# schematic.net
KiCad netlist of a schematic drawn in EAGLE
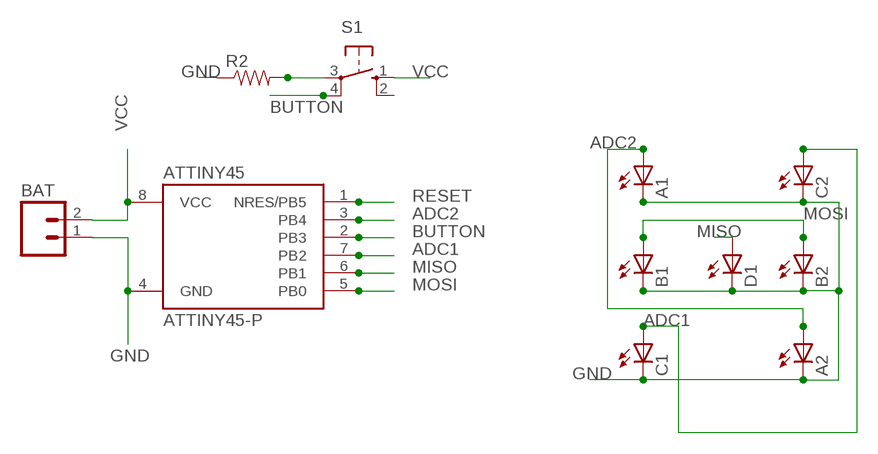
[diagram p0: schematic, sheet 1]

(export (version "E")
  (design (tool "Eeschema 10.0.6"))
  (components
    (comp (ref "A1")
      (value "LED5MM")
      (footprint "eagle-import:LED5MM")
      (libsource (lib "eagle-import") (part "LED5MM"))
    )
    (comp (ref "A2")
      (value "LED5MM")
      (footprint "eagle-import:LED5MM")
      (libsource (lib "eagle-import") (part "LED5MM"))
    )
    (comp (ref "ATTINY45")
      (value "ATTINY45-P")
      (footprint "eagle-import:PDIP08_300MIL")
      (libsource (lib "eagle-import") (part "ATTINY45P-"))
    )
    (comp (ref "B1")
      (value "LED5MM")
      (footprint "eagle-import:LED5MM")
      (libsource (lib "eagle-import") (part "LED5MM"))
    )
    (comp (ref "B2")
      (value "LED5MM")
      (footprint "eagle-import:LED5MM")
      (libsource (lib "eagle-import") (part "LED5MM"))
    )
    (comp (ref "BAT")
      (value "M02PTH")
      (footprint "eagle-import:1X02")
      (libsource (lib "eagle-import") (part "M02PTH"))
    )
    (comp (ref "C1")
      (value "LED5MM")
      (footprint "eagle-import:LED5MM")
      (libsource (lib "eagle-import") (part "LED5MM"))
    )
    (comp (ref "C2")
      (value "LED5MM")
      (footprint "eagle-import:LED5MM")
      (libsource (lib "eagle-import") (part "LED5MM"))
    )
    (comp (ref "D1")
      (value "LED5MM")
      (footprint "eagle-import:LED5MM")
      (libsource (lib "eagle-import") (part "LED5MM"))
    )
    (comp (ref "R2")
      (value "10KOHM-1/6W-5%(PTH)KIT")
      (footprint "eagle-import:AXIAL-0.3-KIT")
      (libsource (lib "eagle-import") (part "10KOHM-1/6W-5%(PTH)KIT"))
    )
    (comp (ref "S1")
      (value "40-XX")
      (footprint "eagle-import:B3F-40XX")
      (fields (field (name "MF") "OMRON COMPONENTS USA") (field (name "MPN") "B3F-4000"))
      (libsource (lib "eagle-import") (part "40-XX"))
    )
  )
  (nets
    (net (code "1") (name "/ADC1") (class "Default")
      (node (ref "ATTINY45") (pin "7") (pinfunction "PB2_7") (pintype "bidirectional"))
      (node (ref "C1") (pin "A") (pinfunction "A_A") (pintype "passive"))
      (node (ref "C2") (pin "A") (pinfunction "A_A") (pintype "passive"))
    )
    (net (code "2") (name "/ADC2") (class "Default")
      (node (ref "A1") (pin "A") (pinfunction "A_A") (pintype "passive"))
      (node (ref "A2") (pin "A") (pinfunction "A_A") (pintype "passive"))
      (node (ref "ATTINY45") (pin "3") (pinfunction "PB4_3") (pintype "bidirectional"))
    )
    (net (code "3") (name "/BUTTON") (class "Default")
      (node (ref "ATTINY45") (pin "2") (pinfunction "PB3_2") (pintype "bidirectional"))
      (node (ref "S1") (pin "4") (pinfunction "P1_4") (pintype "passive"))
    )
    (net (code "4") (name "/GND") (class "Default")
      (node (ref "A1") (pin "K") (pinfunction "C_K") (pintype "passive"))
      (node (ref "A2") (pin "K") (pinfunction "C_K") (pintype "passive"))
      (node (ref "ATTINY45") (pin "4") (pinfunction "GND_4") (pintype "power_in"))
      (node (ref "B1") (pin "K") (pinfunction "C_K") (pintype "passive"))
      (node (ref "B2") (pin "K") (pinfunction "C_K") (pintype "passive"))
      (node (ref "BAT") (pin "1") (pinfunction "1_1") (pintype "passive"))
      (node (ref "C1") (pin "K") (pinfunction "C_K") (pintype "passive"))
      (node (ref "C2") (pin "K") (pinfunction "C_K") (pintype "passive"))
      (node (ref "D1") (pin "K") (pinfunction "C_K") (pintype "passive"))
      (node (ref "R2") (pin "P$1") (pinfunction "1_P$1") (pintype "passive"))
    )
    (net (code "5") (name "/MISO") (class "Default")
      (node (ref "ATTINY45") (pin "6") (pinfunction "PB1_6") (pintype "bidirectional"))
      (node (ref "D1") (pin "A") (pinfunction "A_A") (pintype "passive"))
    )
    (net (code "6") (name "/MOSI") (class "Default")
      (node (ref "ATTINY45") (pin "5") (pinfunction "PB0_5") (pintype "bidirectional"))
      (node (ref "B1") (pin "A") (pinfunction "A_A") (pintype "passive"))
      (node (ref "B2") (pin "A") (pinfunction "A_A") (pintype "passive"))
    )
    (net (code "7") (name "/RESET") (class "Default")
      (node (ref "ATTINY45") (pin "1") (pinfunction "NRES/PB5_1") (pintype "bidirectional"))
    )
    (net (code "8") (name "/VCC") (class "Default")
      (node (ref "ATTINY45") (pin "8") (pinfunction "VCC_8") (pintype "power_in"))
      (node (ref "BAT") (pin "2") (pinfunction "2_2") (pintype "passive"))
      (node (ref "S1") (pin "1") (pinfunction "S_1") (pintype "passive"))
    )
    (net (code "9") (name "Net-(R2-2)") (class "Default")
      (node (ref "R2") (pin "P$2") (pinfunction "2_P$2") (pintype "passive"))
      (node (ref "S1") (pin "3") (pinfunction "P_3") (pintype "passive"))
    )
    (net (code "10") (name "unconnected-(S1-S1-Pad2)") (class "Default")
      (node (ref "S1") (pin "2") (pinfunction "S1_2") (pintype "passive"))
    )
  )
)
